# IF.net
KiCad netlist of a schematic drawn in Altium Designer
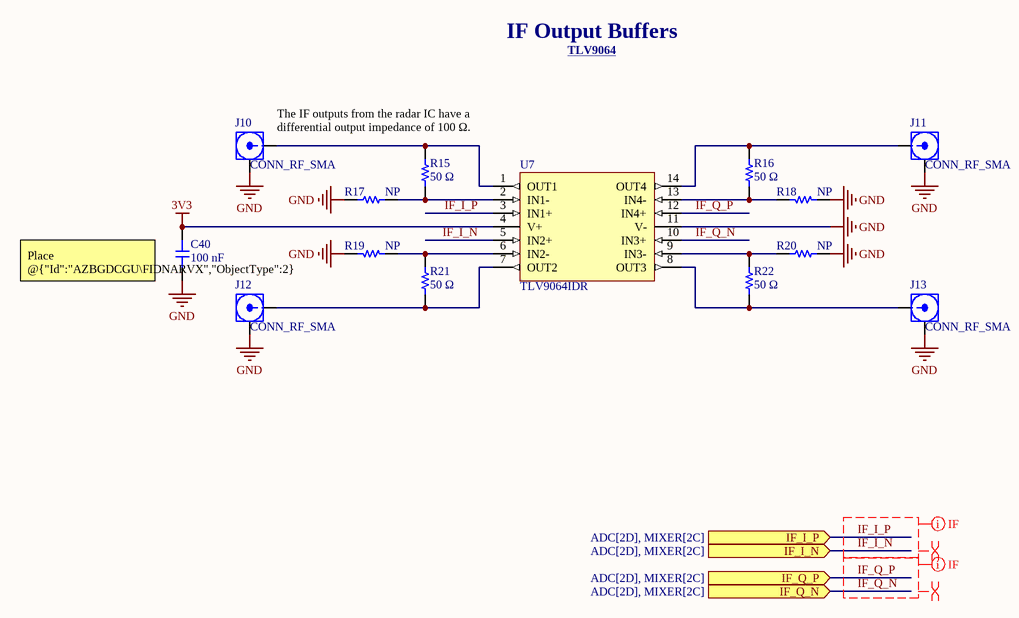
[diagram p0: IF.SchDoc]

(export (version "E")
  (design (tool "Eeschema 10.0.6"))
  (components
    (comp (ref "C40")
      (value "100 nF")
      (footprint "CAP_0402")
      (description "Ceramic Capacitor, Ceramic, 50V, 10% +Tol, 10% -Tol, X7R, 15% TC, 0.1uF, Surface Mount, 0402")
      (fields
        (field (name "MANUFACTURER") "Yageo")
        (field (name "MANUFACTURER PART NUMBER") "CC0402KPX7R9BB104")
      )
      (libsource (lib "Titan") (part "CAP"))
    )
    (comp (ref "J10")
      (value "CONN_RF_SMA")
      (footprint "SMA-J-P-H-ST-TH1")
      (description "RF / Coaxial Connector, SMA Coaxial, Straight Jack, Through Hole Vertical, 50 ohm")
      (fields
        (field (name "MANUFACTURER") "Samtec")
        (field (name "MANUFACTURER PART NUMBER") "SMA-J-P-H-ST-TH1")
      )
      (libsource (lib "Titan") (part "CONN_RF_SMA"))
    )
    (comp (ref "J11")
      (value "CONN_RF_SMA")
      (footprint "SMA-J-P-H-ST-TH1")
      (description "RF / Coaxial Connector, SMA Coaxial, Straight Jack, Through Hole Vertical, 50 ohm")
      (fields
        (field (name "MANUFACTURER") "Samtec")
        (field (name "MANUFACTURER PART NUMBER") "SMA-J-P-H-ST-TH1")
      )
      (libsource (lib "Titan") (part "CONN_RF_SMA"))
    )
    (comp (ref "J12")
      (value "CONN_RF_SMA")
      (footprint "SMA-J-P-H-ST-TH1")
      (description "RF / Coaxial Connector, SMA Coaxial, Straight Jack, Through Hole Vertical, 50 ohm")
      (fields
        (field (name "MANUFACTURER") "Samtec")
        (field (name "MANUFACTURER PART NUMBER") "SMA-J-P-H-ST-TH1")
      )
      (libsource (lib "Titan") (part "CONN_RF_SMA"))
    )
    (comp (ref "J13")
      (value "CONN_RF_SMA")
      (footprint "SMA-J-P-H-ST-TH1")
      (description "RF / Coaxial Connector, SMA Coaxial, Straight Jack, Through Hole Vertical, 50 ohm")
      (fields
        (field (name "MANUFACTURER") "Samtec")
        (field (name "MANUFACTURER PART NUMBER") "SMA-J-P-H-ST-TH1")
      )
      (libsource (lib "Titan") (part "CONN_RF_SMA"))
    )
    (comp (ref "R15")
      (value "50 Ω")
      (footprint "RES_0603")
      (description "100mW Thin Film Resistor ±50ppm/℃ ±0.1% 50Ω 0603 Chip Resistor - Surface Mount ROHS")
      (fields
        (field (name "MANUFACTURER") "Yageo")
        (field (name "MANUFACTURER PART NUMBER") "RT0603BRE0750RL")
      )
      (libsource (lib "Titan") (part "RES"))
    )
    (comp (ref "R16")
      (value "50 Ω")
      (footprint "RES_0603")
      (description "100mW Thin Film Resistor ±50ppm/℃ ±0.1% 50Ω 0603 Chip Resistor - Surface Mount ROHS")
      (fields
        (field (name "MANUFACTURER") "Yageo")
        (field (name "MANUFACTURER PART NUMBER") "RT0603BRE0750RL")
      )
      (libsource (lib "Titan") (part "RES"))
    )
    (comp (ref "R17")
      (value "NP")
      (footprint "RES_0603")
      (description "Resistor SMD Generic")
      (libsource (lib "Titan") (part "RES"))
    )
    (comp (ref "R18")
      (value "NP")
      (footprint "RES_0603")
      (description "Resistor SMD Generic")
      (libsource (lib "Titan") (part "RES"))
    )
    (comp (ref "R19")
      (value "NP")
      (footprint "RES_0603")
      (description "Resistor SMD Generic")
      (libsource (lib "Titan") (part "RES"))
    )
    (comp (ref "R20")
      (value "NP")
      (footprint "RES_0603")
      (description "Resistor SMD Generic")
      (libsource (lib "Titan") (part "RES"))
    )
    (comp (ref "R21")
      (value "50 Ω")
      (footprint "RES_0603")
      (description "100mW Thin Film Resistor ±50ppm/℃ ±0.1% 50Ω 0603 Chip Resistor - Surface Mount ROHS")
      (fields
        (field (name "MANUFACTURER") "Yageo")
        (field (name "MANUFACTURER PART NUMBER") "RT0603BRE0750RL")
      )
      (libsource (lib "Titan") (part "RES"))
    )
    (comp (ref "R22")
      (value "50 Ω")
      (footprint "RES_0603")
      (description "100mW Thin Film Resistor ±50ppm/℃ ±0.1% 50Ω 0603 Chip Resistor - Surface Mount ROHS")
      (fields
        (field (name "MANUFACTURER") "Yageo")
        (field (name "MANUFACTURER PART NUMBER") "RT0603BRE0750RL")
      )
      (libsource (lib "Titan") (part "RES"))
    )
    (comp (ref "U7")
      (value "TLV9064IDR")
      (footprint "TLV9064IDR")
      (description "Quad, 5.5-V, 10-MHz, RRIO operational amplifier for cost-optimized applications 14-SOIC -40 to 125")
      (fields (field (name "MANUFACTURER") "Texas Instruments"))
      (libsource (lib "Titan") (part "TLV9064IDR"))
    )
  )
  (nets
    (net (code "1") (name "/IF_I_N") (class "Default")
      (node (ref "U7") (pin "5") (pinfunction "IN2+_5") (pintype "input"))
    )
    (net (code "2") (name "/IF_I_P") (class "Default")
      (node (ref "U7") (pin "3") (pinfunction "IN1+_3") (pintype "input"))
    )
    (net (code "3") (name "/IF_Q_N") (class "Default")
      (node (ref "U7") (pin "10") (pinfunction "IN3+_10") (pintype "input"))
    )
    (net (code "4") (name "/IF_Q_P") (class "Default")
      (node (ref "U7") (pin "12") (pinfunction "IN4+_12") (pintype "input"))
    )
    (net (code "5") (name "3V3") (class "Default")
      (node (ref "C40") (pin "2") (pintype "passive"))
      (node (ref "U7") (pin "4") (pinfunction "V+_4") (pintype "power_in"))
    )
    (net (code "6") (name "GND") (class "Default")
      (node (ref "C40") (pin "1") (pintype "passive"))
      (node (ref "J10") (pin "2") (pintype "passive"))
      (node (ref "J11") (pin "2") (pintype "passive"))
      (node (ref "J12") (pin "2") (pintype "passive"))
      (node (ref "J13") (pin "2") (pintype "passive"))
      (node (ref "R17") (pin "2") (pintype "passive"))
      (node (ref "R18") (pin "2") (pintype "passive"))
      (node (ref "R19") (pin "2") (pintype "passive"))
      (node (ref "R20") (pin "2") (pintype "passive"))
      (node (ref "U7") (pin "11") (pinfunction "V-_11") (pintype "power_in"))
    )
    (net (code "7") (name "Net-(U7-IN1-)") (class "Default")
      (node (ref "R15") (pin "1") (pintype "passive"))
      (node (ref "R17") (pin "1") (pintype "passive"))
      (node (ref "U7") (pin "2") (pinfunction "IN1-_2") (pintype "input"))
    )
    (net (code "8") (name "Net-(U7-IN2-)") (class "Default")
      (node (ref "R19") (pin "1") (pintype "passive"))
      (node (ref "R21") (pin "1") (pintype "passive"))
      (node (ref "U7") (pin "6") (pinfunction "IN2-_6") (pintype "input"))
    )
    (net (code "9") (name "Net-(U7-IN3-)") (class "Default")
      (node (ref "R20") (pin "1") (pintype "passive"))
      (node (ref "R22") (pin "1") (pintype "passive"))
      (node (ref "U7") (pin "9") (pinfunction "IN3-_9") (pintype "input"))
    )
    (net (code "10") (name "Net-(U7-IN4-)") (class "Default")
      (node (ref "R16") (pin "1") (pintype "passive"))
      (node (ref "R18") (pin "1") (pintype "passive"))
      (node (ref "U7") (pin "13") (pinfunction "IN4-_13") (pintype "input"))
    )
    (net (code "11") (name "Net-(U7-OUT1)") (class "Default")
      (node (ref "J10") (pin "1") (pintype "passive"))
      (node (ref "R15") (pin "2") (pintype "passive"))
      (node (ref "U7") (pin "1") (pinfunction "OUT1_1") (pintype "output"))
    )
    (net (code "12") (name "Net-(U7-OUT2)") (class "Default")
      (node (ref "J12") (pin "1") (pintype "passive"))
      (node (ref "R21") (pin "2") (pintype "passive"))
      (node (ref "U7") (pin "7") (pinfunction "OUT2_7") (pintype "output"))
    )
    (net (code "13") (name "Net-(U7-OUT3)") (class "Default")
      (node (ref "J13") (pin "1") (pintype "passive"))
      (node (ref "R22") (pin "2") (pintype "passive"))
      (node (ref "U7") (pin "8") (pinfunction "OUT3_8") (pintype "output"))
    )
    (net (code "14") (name "Net-(U7-OUT4)") (class "Default")
      (node (ref "J11") (pin "1") (pintype "passive"))
      (node (ref "R16") (pin "2") (pintype "passive"))
      (node (ref "U7") (pin "14") (pinfunction "OUT4_14") (pintype "output"))
    )
  )
)
